# PCB_Business_Card.net
KiCad netlist of a schematic drawn in Altium Designer
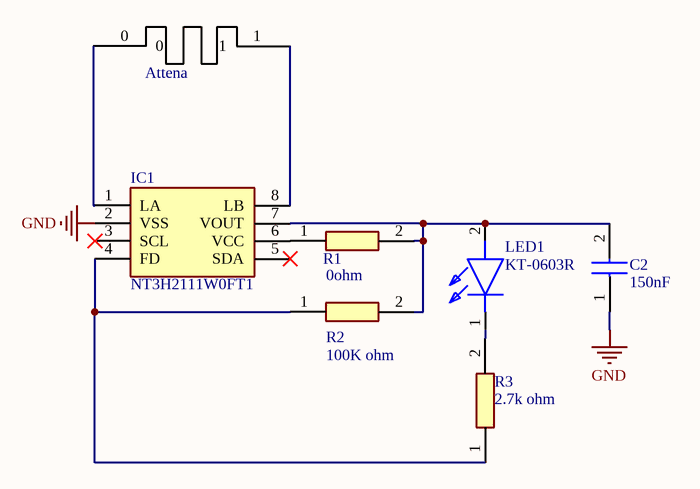
[diagram p0: PCB_Business_Card.SchDoc]

(export (version "E")
  (design (tool "Eeschema 10.0.6"))
  (components
    (comp (ref "*")
      (value "Attena")
      (footprint "PCBComponent_1 - duplicate")
      (libsource (lib "Schlib1") (part "Attena"))
    )
    (comp (ref "C2")
      (value "150nF")
      (footprint "PcbLib1:CAPC1608X90N")
      (description "Capacitor")
      (fields
        (field (name "MANUFACTURER_PART_NUMBER") "CC0603KRX7R7BB154")
        (field (name "MOUSER PART NUMBER") "603-CC603KRX7R7BB154")
      )
      (libsource (lib "Schlib1") (part "CC0603KRX7R7BB154"))
    )
    (comp (ref "IC1")
      (value "NT3H2111W0FT1")
      (footprint "PcbLib1:SOIC127P600X175-8N")
      (description "Integrated Circuit")
      (libsource (lib "Schlib1") (part "NT3H2111W0FT1"))
    )
    (comp (ref "LED1")
      (value "KT-0603R")
      (footprint "PcbLib1:LEDC1608X70N")
      (description "LED")
      (libsource (lib "Schlib1") (part "KT-0603R"))
    )
    (comp (ref "R1")
      (value "0ohm")
      (footprint "PcbLib1:RESC1608X55N")
      (description "Resistor")
      (fields
        (field (name "MANUFACTURER_PART_NUMBER") "0603WAJ0000T5E")
        (field (name "MOUSER PART NUMBER") "303-0603WAJ0000T5E")
      )
      (libsource (lib "Schlib1") (part "0603WAJ0000T5E"))
    )
    (comp (ref "R2")
      (value "100K ohm")
      (footprint "PcbLib1:RESC1608X55N")
      (description "Resistor")
      (fields
        (field (name "MANUFACTURER_PART_NUMBER") "RC0603FR-07100KL")
        (field (name "MOUSER PART NUMBER") "603-RC0603FR-07100KL")
      )
      (libsource (lib "Schlib1") (part "RC0603FR-07100KL"))
    )
    (comp (ref "R3")
      (value "2.7k ohm")
      (footprint "PcbLib1:RESC1608X55N")
      (description "Resistor")
      (fields (field (name "MANUFACTURER_PART_NUMBER") "0603WAF2701T5E"))
      (libsource (lib "Schlib1") (part "0603WAF2701T5E"))
    )
  )
  (nets
    (net (code "1") (name "GND") (class "Default")
      (node (ref "C2") (pin "1") (pinfunction "1_1") (pintype "passive"))
      (node (ref "IC1") (pin "2") (pinfunction "VSS_2") (pintype "passive"))
    )
    (net (code "2") (name "Net-(IC1-FD)") (class "Default")
      (node (ref "IC1") (pin "4") (pinfunction "FD_4") (pintype "passive"))
      (node (ref "R2") (pin "1") (pinfunction "1_1") (pintype "passive"))
      (node (ref "R3") (pin "1") (pinfunction "1_1") (pintype "passive"))
    )
    (net (code "3") (name "Net-(IC1-LA)") (class "Default")
      (node (ref "*") (pin "0") (pinfunction "0_0") (pintype "passive"))
      (node (ref "IC1") (pin "1") (pinfunction "LA_1") (pintype "passive"))
    )
    (net (code "4") (name "Net-(IC1-LB)") (class "Default")
      (node (ref "*") (pin "1") (pinfunction "1_1") (pintype "passive"))
      (node (ref "IC1") (pin "8") (pinfunction "LB_8") (pintype "passive"))
    )
    (net (code "5") (name "Net-(IC1-VCC)") (class "Default")
      (node (ref "IC1") (pin "6") (pinfunction "VCC_6") (pintype "passive"))
      (node (ref "R1") (pin "1") (pinfunction "1_1") (pintype "passive"))
    )
    (net (code "6") (name "Net-(IC1-VOUT)") (class "Default")
      (node (ref "C2") (pin "2") (pinfunction "2_2") (pintype "passive"))
      (node (ref "IC1") (pin "7") (pinfunction "VOUT_7") (pintype "passive"))
      (node (ref "LED1") (pin "2") (pinfunction "A_2") (pintype "passive"))
      (node (ref "R1") (pin "2") (pinfunction "2_2") (pintype "passive"))
      (node (ref "R2") (pin "2") (pinfunction "2_2") (pintype "passive"))
    )
    (net (code "7") (name "Net-(LED1-K)") (class "Default")
      (node (ref "LED1") (pin "1") (pinfunction "K_1") (pintype "passive"))
      (node (ref "R3") (pin "2") (pinfunction "2_2") (pintype "passive"))
    )
    (net (code "8") (name "unconnected-(IC1-SCL-Pad3)") (class "Default")
      (node (ref "IC1") (pin "3") (pinfunction "SCL_3") (pintype "passive+no_connect"))
    )
    (net (code "9") (name "unconnected-(IC1-SDA-Pad5)") (class "Default")
      (node (ref "IC1") (pin "5") (pinfunction "SDA_5") (pintype "passive+no_connect"))
    )
  )
)
